# eth_10base-t1s_phy.net
KiCad netlist of a schematic drawn in Altium Designer
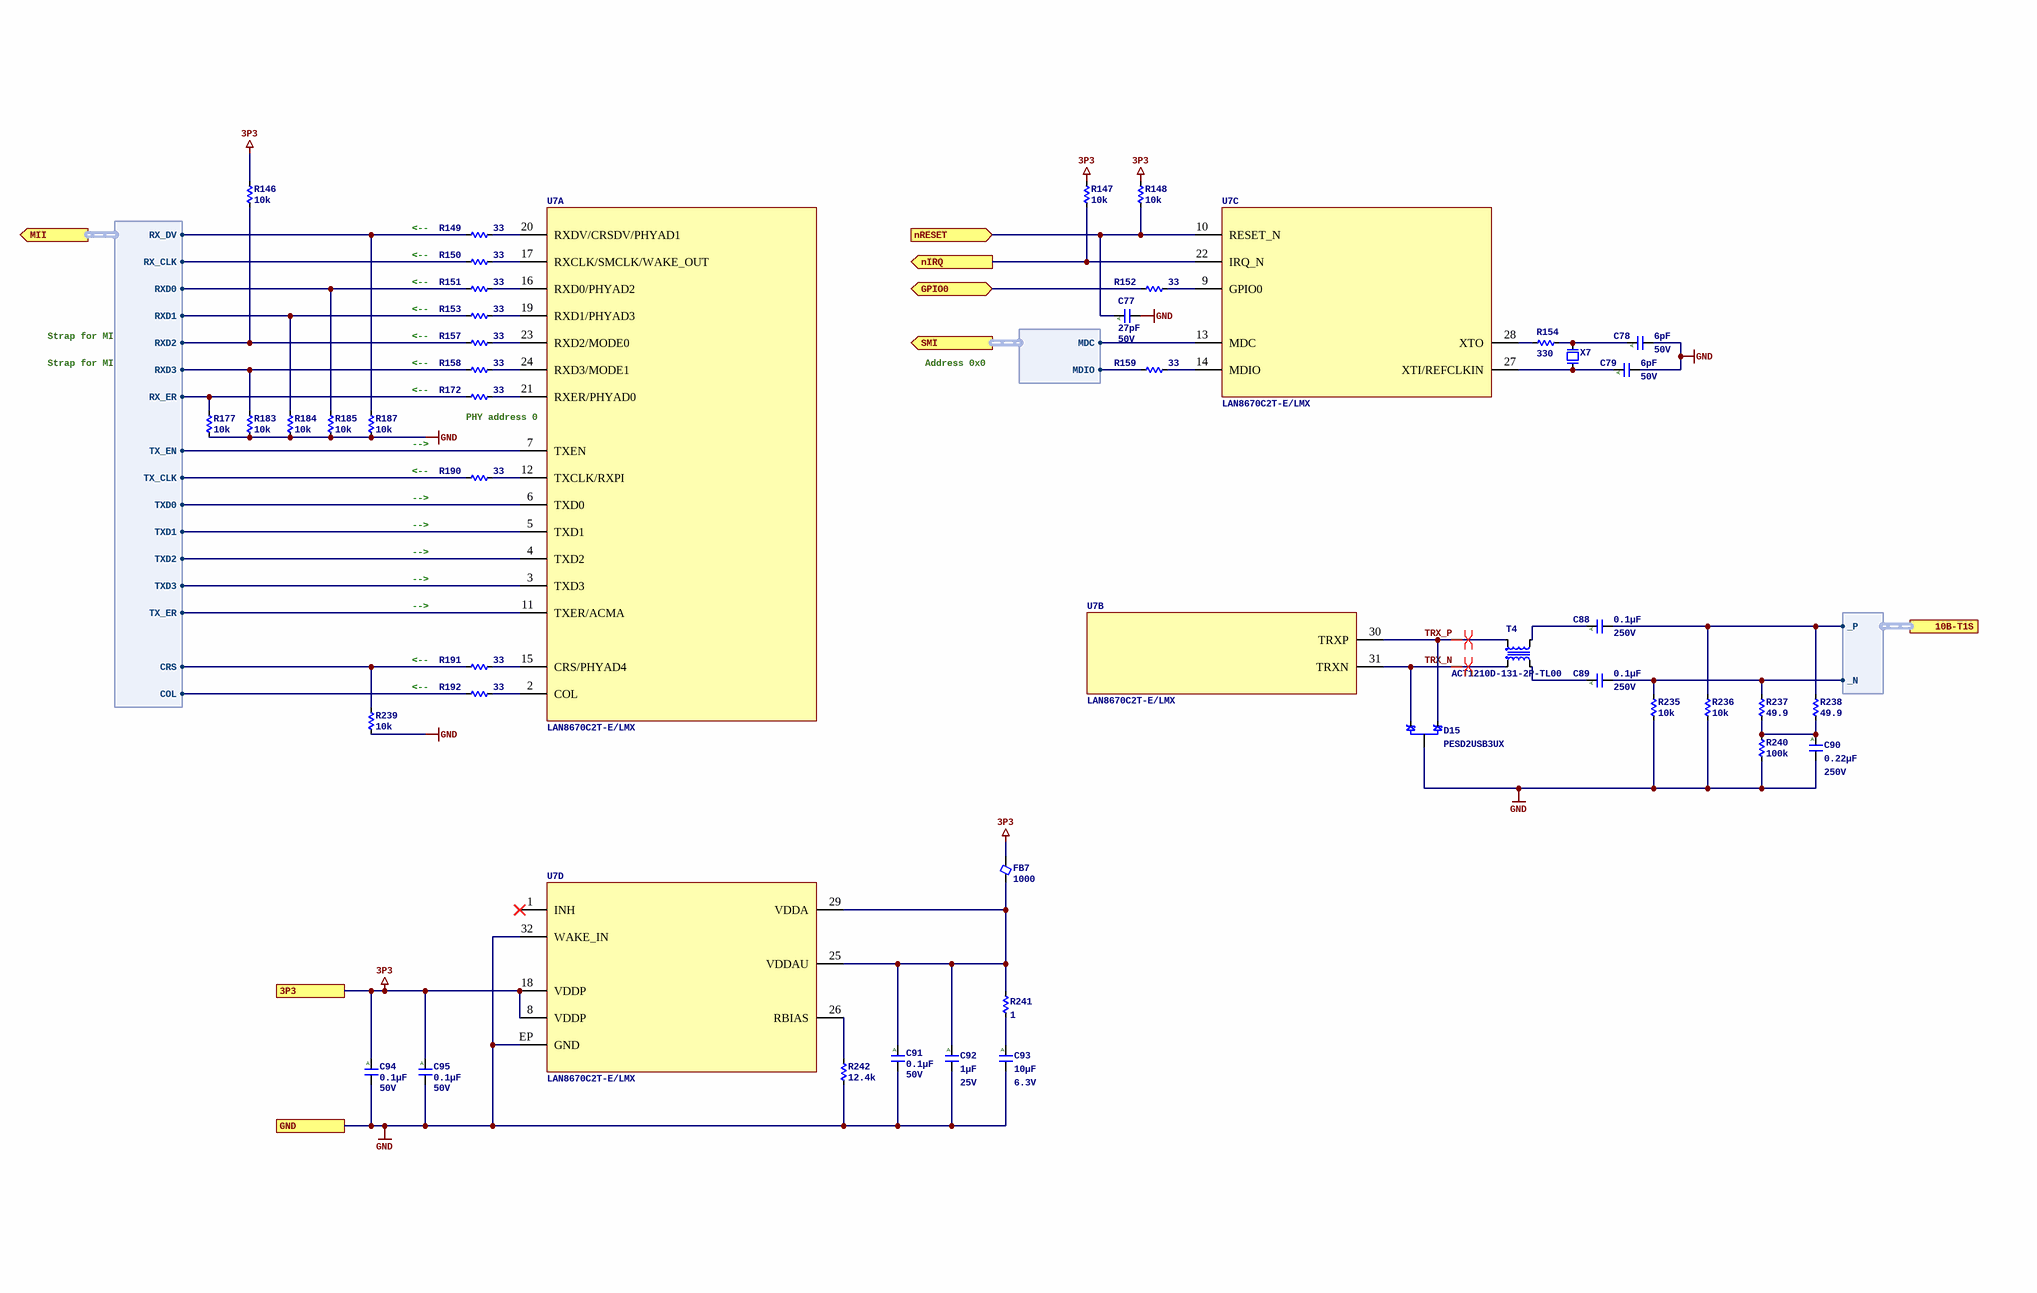
[diagram p0: eth_10base-t1s_phy.SchDoc]

(export (version "E")
  (design (tool "Eeschema 10.0.6"))
  (components
    (comp (ref "C77")
      (value "CGA2B2C0G1H270J050BA")
      (footprint "C0402_0.55MM")
      (description "CAP CER 27PF 50V C0G 0402")
      (fields
        (field (name "CAPACITANCE") "27pF")
        (field (name "VOLTAGE - RATED") "50V")
        (field (name "TOLERANCE") "±5%")
        (field (name "MANUFACTURER") "TDK Corporation")
      )
      (libsource (lib "sscp") (part "__template_cap_auto"))
    )
    (comp (ref "C78")
      (value "CGA2B2C0G1H060D050BA")
      (footprint "C0402_0.55MM")
      (description "CAP CER 6PF 50V C0G 0402")
      (fields
        (field (name "CAPACITANCE") "6pF")
        (field (name "VOLTAGE - RATED") "50V")
        (field (name "TOLERANCE") "±0.5pF")
        (field (name "MANUFACTURER") "TDK Corporation")
      )
      (libsource (lib "sscp") (part "__template_cap_auto"))
    )
    (comp (ref "C79")
      (value "CGA2B2C0G1H060D050BA")
      (footprint "C0402_0.55MM")
      (description "CAP CER 6PF 50V C0G 0402")
      (fields
        (field (name "CAPACITANCE") "6pF")
        (field (name "VOLTAGE - RATED") "50V")
        (field (name "TOLERANCE") "±0.5pF")
        (field (name "MANUFACTURER") "TDK Corporation")
      )
      (libsource (lib "sscp") (part "__template_cap_auto"))
    )
    (comp (ref "C88")
      (value "CGA5L3X7R2E104K160AA")
      (footprint "C1206_1.80MM")
      (description "CAP CER 0.1UF 250V X7R 1206")
      (fields
        (field (name "CAPACITANCE") "0.1µF")
        (field (name "VOLTAGE - RATED") "250V")
        (field (name "TOLERANCE") "±10%")
        (field (name "MANUFACTURER") "TDK Corporation")
      )
      (libsource (lib "sscp") (part "__template_cap_auto"))
    )
    (comp (ref "C89")
      (value "CGA5L3X7R2E104K160AA")
      (footprint "C1206_1.80MM")
      (description "CAP CER 0.1UF 250V X7R 1206")
      (fields
        (field (name "CAPACITANCE") "0.1µF")
        (field (name "VOLTAGE - RATED") "250V")
        (field (name "TOLERANCE") "±10%")
        (field (name "MANUFACTURER") "TDK Corporation")
      )
      (libsource (lib "sscp") (part "__template_cap_auto"))
    )
    (comp (ref "C90")
      (value "CGA6M3X7R2E224K200AA")
      (footprint "C1210_2.20MM")
      (description "CAP CER 0.22UF 250V X7R 1210")
      (fields
        (field (name "CAPACITANCE") "0.22µF")
        (field (name "VOLTAGE - RATED") "250V")
        (field (name "TOLERANCE") "±10%")
        (field (name "MANUFACTURER") "TDK Corporation")
      )
      (libsource (lib "sscp") (part "__template_cap_auto"))
    )
    (comp (ref "C91")
      (value "CGA2B3X7R1H104M050BB")
      (footprint "C0402_0.55MM")
      (description "CAP CER 0.1UF 50V X7R 0402")
      (fields
        (field (name "CAPACITANCE") "0.1µF")
        (field (name "VOLTAGE - RATED") "50V")
        (field (name "TOLERANCE") "±20%")
        (field (name "MANUFACTURER") "TDK Corporation")
      )
      (libsource (lib "sscp") (part "__template_cap_auto"))
    )
    (comp (ref "C92")
      (value "CGJ3E1X7R1E105K080AC")
      (footprint "C0603_0.80MM")
      (description "CAP CER 1UF 25V X7R 0603")
      (fields
        (field (name "CAPACITANCE") "1µF")
        (field (name "VOLTAGE - RATED") "25V")
        (field (name "TOLERANCE") "±10%")
        (field (name "MANUFACTURER") "TDK Corporation")
      )
      (libsource (lib "sscp") (part "__template_cap_auto"))
    )
    (comp (ref "C93")
      (value "CGA4J1X7R0J106M125AC")
      (footprint "C0805_1.45MM")
      (description "CAP CER 10UF 6.3V X7R 0805")
      (fields
        (field (name "CAPACITANCE") "10µF")
        (field (name "VOLTAGE - RATED") "6.3V")
        (field (name "TOLERANCE") "±20%")
        (field (name "MANUFACTURER") "TDK Corporation")
      )
      (libsource (lib "sscp") (part "__template_cap_auto"))
    )
    (comp (ref "C94")
      (value "CGA2B3X7R1H104M050BB")
      (footprint "C0402_0.55MM")
      (description "CAP CER 0.1UF 50V X7R 0402")
      (fields
        (field (name "CAPACITANCE") "0.1µF")
        (field (name "VOLTAGE - RATED") "50V")
        (field (name "TOLERANCE") "±20%")
        (field (name "MANUFACTURER") "TDK Corporation")
      )
      (libsource (lib "sscp") (part "__template_cap_auto"))
    )
    (comp (ref "C95")
      (value "CGA2B3X7R1H104M050BB")
      (footprint "C0402_0.55MM")
      (description "CAP CER 0.1UF 50V X7R 0402")
      (fields
        (field (name "CAPACITANCE") "0.1µF")
        (field (name "VOLTAGE - RATED") "50V")
        (field (name "TOLERANCE") "±20%")
        (field (name "MANUFACTURER") "TDK Corporation")
      )
      (libsource (lib "sscp") (part "__template_cap_auto"))
    )
    (comp (ref "D15")
      (value "PESD2USB3UX")
      (footprint "3SOT23")
      (description "DIODE ESD USB SOT-23")
      (fields (field (name "MANUFACTURER") "Nexperia USA Inc."))
      (libsource (lib "SSCP") (part "TVS_PESD2USB3UX-T"))
    )
    (comp (ref "FB7")
      (value "MPZ2012S102AT000")
      (footprint "FB0805_1.05MM")
      (description "FERRITE BEAD 1 KOHM 0805 1LN")
      (fields
        (field (name "IMPEDANCE (OHMS @ 100MHZ)") "1000")
        (field (name "MANUFACTURER") "TDK Corporation")
      )
      (libsource (lib "sscp") (part "__template_ferrite"))
    )
    (comp (ref "R146")
      (value "ERJ-2RKF1002X")
      (footprint "R0402_0.40MM")
      (description "RES SMD 10K OHM 1% 1/10W 0402")
      (fields
        (field (name "RESISTANCE") "10k")
        (field (name "TOLERANCE") "±1%")
        (field (name "MANUFACTURER") "Panasonic Electronic Components")
      )
      (libsource (lib "sscp") (part "__template_resistor"))
    )
    (comp (ref "R147")
      (value "ERJ-2RKF1002X")
      (footprint "R0402_0.40MM")
      (description "RES SMD 10K OHM 1% 1/10W 0402")
      (fields
        (field (name "RESISTANCE") "10k")
        (field (name "TOLERANCE") "±1%")
        (field (name "MANUFACTURER") "Panasonic Electronic Components")
      )
      (libsource (lib "sscp") (part "__template_resistor"))
    )
    (comp (ref "R148")
      (value "ERJ-2RKF1002X")
      (footprint "R0402_0.40MM")
      (description "RES SMD 10K OHM 1% 1/10W 0402")
      (fields
        (field (name "RESISTANCE") "10k")
        (field (name "TOLERANCE") "±1%")
        (field (name "MANUFACTURER") "Panasonic Electronic Components")
      )
      (libsource (lib "sscp") (part "__template_resistor"))
    )
    (comp (ref "R149")
      (value "ERJ-2RKF33R0X")
      (footprint "R0402_0.40MM")
      (description "RES SMD 33 OHM 1% 1/10W 0402")
      (fields
        (field (name "RESISTANCE") "33")
        (field (name "TOLERANCE") "±1%")
        (field (name "MANUFACTURER") "Panasonic Electronic Components")
      )
      (libsource (lib "sscp") (part "__template_resistor"))
    )
    (comp (ref "R150")
      (value "ERJ-2RKF33R0X")
      (footprint "R0402_0.40MM")
      (description "RES SMD 33 OHM 1% 1/10W 0402")
      (fields
        (field (name "RESISTANCE") "33")
        (field (name "TOLERANCE") "±1%")
        (field (name "MANUFACTURER") "Panasonic Electronic Components")
      )
      (libsource (lib "sscp") (part "__template_resistor"))
    )
    (comp (ref "R151")
      (value "ERJ-2RKF33R0X")
      (footprint "R0402_0.40MM")
      (description "RES SMD 33 OHM 1% 1/10W 0402")
      (fields
        (field (name "RESISTANCE") "33")
        (field (name "TOLERANCE") "±1%")
        (field (name "MANUFACTURER") "Panasonic Electronic Components")
      )
      (libsource (lib "sscp") (part "__template_resistor"))
    )
    (comp (ref "R152")
      (value "ERJ-2RKF33R0X")
      (footprint "R0402_0.40MM")
      (description "RES SMD 33 OHM 1% 1/10W 0402")
      (fields
        (field (name "RESISTANCE") "33")
        (field (name "TOLERANCE") "±1%")
        (field (name "MANUFACTURER") "Panasonic Electronic Components")
      )
      (libsource (lib "sscp") (part "__template_resistor"))
    )
    (comp (ref "R153")
      (value "ERJ-2RKF33R0X")
      (footprint "R0402_0.40MM")
      (description "RES SMD 33 OHM 1% 1/10W 0402")
      (fields
        (field (name "RESISTANCE") "33")
        (field (name "TOLERANCE") "±1%")
        (field (name "MANUFACTURER") "Panasonic Electronic Components")
      )
      (libsource (lib "sscp") (part "__template_resistor"))
    )
    (comp (ref "R154")
      (value "ERJ-PA2F3300X")
      (footprint "R0402_0.40MM")
      (description "RES SMD 330 OHM 1% 1/5W 0402")
      (fields
        (field (name "RESISTANCE") "330")
        (field (name "TOLERANCE") "±1%")
        (field (name "MANUFACTURER") "Panasonic Electronic Components")
      )
      (libsource (lib "sscp") (part "__template_resistor"))
    )
    (comp (ref "R157")
      (value "ERJ-2RKF33R0X")
      (footprint "R0402_0.40MM")
      (description "RES SMD 33 OHM 1% 1/10W 0402")
      (fields
        (field (name "RESISTANCE") "33")
        (field (name "TOLERANCE") "±1%")
        (field (name "MANUFACTURER") "Panasonic Electronic Components")
      )
      (libsource (lib "sscp") (part "__template_resistor"))
    )
    (comp (ref "R158")
      (value "ERJ-2RKF33R0X")
      (footprint "R0402_0.40MM")
      (description "RES SMD 33 OHM 1% 1/10W 0402")
      (fields
        (field (name "RESISTANCE") "33")
        (field (name "TOLERANCE") "±1%")
        (field (name "MANUFACTURER") "Panasonic Electronic Components")
      )
      (libsource (lib "sscp") (part "__template_resistor"))
    )
    (comp (ref "R159")
      (value "ERJ-2RKF33R0X")
      (footprint "R0402_0.40MM")
      (description "RES SMD 33 OHM 1% 1/10W 0402")
      (fields
        (field (name "RESISTANCE") "33")
        (field (name "TOLERANCE") "±1%")
        (field (name "MANUFACTURER") "Panasonic Electronic Components")
      )
      (libsource (lib "sscp") (part "__template_resistor"))
    )
    (comp (ref "R172")
      (value "ERJ-2RKF33R0X")
      (footprint "R0402_0.40MM")
      (description "RES SMD 33 OHM 1% 1/10W 0402")
      (fields
        (field (name "RESISTANCE") "33")
        (field (name "TOLERANCE") "±1%")
        (field (name "MANUFACTURER") "Panasonic Electronic Components")
      )
      (libsource (lib "sscp") (part "__template_resistor"))
    )
    (comp (ref "R177")
      (value "ERJ-2RKF1002X")
      (footprint "R0402_0.40MM")
      (description "RES SMD 10K OHM 1% 1/10W 0402")
      (fields
        (field (name "RESISTANCE") "10k")
        (field (name "TOLERANCE") "±1%")
        (field (name "MANUFACTURER") "Panasonic Electronic Components")
      )
      (libsource (lib "sscp") (part "__template_resistor"))
    )
    (comp (ref "R183")
      (value "ERJ-2RKF1002X")
      (footprint "R0402_0.40MM")
      (description "RES SMD 10K OHM 1% 1/10W 0402")
      (fields
        (field (name "RESISTANCE") "10k")
        (field (name "TOLERANCE") "±1%")
        (field (name "MANUFACTURER") "Panasonic Electronic Components")
      )
      (libsource (lib "sscp") (part "__template_resistor"))
    )
    (comp (ref "R184")
      (value "ERJ-2RKF1002X")
      (footprint "R0402_0.40MM")
      (description "RES SMD 10K OHM 1% 1/10W 0402")
      (fields
        (field (name "RESISTANCE") "10k")
        (field (name "TOLERANCE") "±1%")
        (field (name "MANUFACTURER") "Panasonic Electronic Components")
      )
      (libsource (lib "sscp") (part "__template_resistor"))
    )
    (comp (ref "R185")
      (value "ERJ-2RKF1002X")
      (footprint "R0402_0.40MM")
      (description "RES SMD 10K OHM 1% 1/10W 0402")
      (fields
        (field (name "RESISTANCE") "10k")
        (field (name "TOLERANCE") "±1%")
        (field (name "MANUFACTURER") "Panasonic Electronic Components")
      )
      (libsource (lib "sscp") (part "__template_resistor"))
    )
    (comp (ref "R187")
      (value "ERJ-2RKF1002X")
      (footprint "R0402_0.40MM")
      (description "RES SMD 10K OHM 1% 1/10W 0402")
      (fields
        (field (name "RESISTANCE") "10k")
        (field (name "TOLERANCE") "±1%")
        (field (name "MANUFACTURER") "Panasonic Electronic Components")
      )
      (libsource (lib "sscp") (part "__template_resistor"))
    )
    (comp (ref "R190")
      (value "ERJ-2RKF33R0X")
      (footprint "R0402_0.40MM")
      (description "RES SMD 33 OHM 1% 1/10W 0402")
      (fields
        (field (name "RESISTANCE") "33")
        (field (name "TOLERANCE") "±1%")
        (field (name "MANUFACTURER") "Panasonic Electronic Components")
      )
      (libsource (lib "sscp") (part "__template_resistor"))
    )
    (comp (ref "R191")
      (value "ERJ-2RKF33R0X")
      (footprint "R0402_0.40MM")
      (description "RES SMD 33 OHM 1% 1/10W 0402")
      (fields
        (field (name "RESISTANCE") "33")
        (field (name "TOLERANCE") "±1%")
        (field (name "MANUFACTURER") "Panasonic Electronic Components")
      )
      (libsource (lib "sscp") (part "__template_resistor"))
    )
    (comp (ref "R192")
      (value "ERJ-2RKF33R0X")
      (footprint "R0402_0.40MM")
      (description "RES SMD 33 OHM 1% 1/10W 0402")
      (fields
        (field (name "RESISTANCE") "33")
        (field (name "TOLERANCE") "±1%")
        (field (name "MANUFACTURER") "Panasonic Electronic Components")
      )
      (libsource (lib "sscp") (part "__template_resistor"))
    )
    (comp (ref "R235")
      (value "ERJ-8ENF1002V")
      (footprint "R1206_0.70MM")
      (description "RES SMD 10K OHM 1% 1/4W 1206")
      (fields
        (field (name "RESISTANCE") "10k")
        (field (name "TOLERANCE") "±1%")
        (field (name "MANUFACTURER") "Panasonic Electronic Components")
      )
      (libsource (lib "sscp") (part "__template_resistor"))
    )
    (comp (ref "R236")
      (value "ERJ-8ENF1002V")
      (footprint "R1206_0.70MM")
      (description "RES SMD 10K OHM 1% 1/4W 1206")
      (fields
        (field (name "RESISTANCE") "10k")
        (field (name "TOLERANCE") "±1%")
        (field (name "MANUFACTURER") "Panasonic Electronic Components")
      )
      (libsource (lib "sscp") (part "__template_resistor"))
    )
    (comp (ref "R237")
      (value "ERJ-8ENF49R9V")
      (footprint "R1206_0.70MM")
      (description "RES SMD 49.9 OHM 1% 1/4W 1206")
      (fields
        (field (name "RESISTANCE") "49.9")
        (field (name "TOLERANCE") "±1%")
        (field (name "MANUFACTURER") "Panasonic Electronic Components")
      )
      (libsource (lib "sscp") (part "__template_resistor"))
    )
    (comp (ref "R238")
      (value "ERJ-8ENF49R9V")
      (footprint "R1206_0.70MM")
      (description "RES SMD 49.9 OHM 1% 1/4W 1206")
      (fields
        (field (name "RESISTANCE") "49.9")
        (field (name "TOLERANCE") "±1%")
        (field (name "MANUFACTURER") "Panasonic Electronic Components")
      )
      (libsource (lib "sscp") (part "__template_resistor"))
    )
    (comp (ref "R239")
      (value "ERJ-2RKF1002X")
      (footprint "R0402_0.40MM")
      (description "RES SMD 10K OHM 1% 1/10W 0402")
      (fields
        (field (name "RESISTANCE") "10k")
        (field (name "TOLERANCE") "±1%")
        (field (name "MANUFACTURER") "Panasonic Electronic Components")
      )
      (libsource (lib "sscp") (part "__template_resistor"))
    )
    (comp (ref "R240")
      (value "ERJ-8ENF1003V")
      (footprint "R1206_0.70MM")
      (description "RES SMD 100K OHM 1% 1/4W 1206")
      (fields
        (field (name "RESISTANCE") "100k")
        (field (name "TOLERANCE") "±1%")
        (field (name "MANUFACTURER") "Panasonic Electronic Components")
      )
      (libsource (lib "sscp") (part "__template_resistor"))
    )
    (comp (ref "R241")
      (value "ERJ-2BQF1R0X")
      (footprint "R0402_0.40MM")
      (description "RES SMD 1 OHM 1% 1/6W 0402")
      (fields
        (field (name "RESISTANCE") "1")
        (field (name "TOLERANCE") "±1%")
        (field (name "MANUFACTURER") "Panasonic Electronic Components")
      )
      (libsource (lib "sscp") (part "__template_resistor"))
    )
    (comp (ref "R242")
      (value "ERJ-2RKF1242X")
      (footprint "R0402_0.40MM")
      (description "RES SMD 12.4K OHM 1% 1/10W 0402")
      (fields
        (field (name "RESISTANCE") "12.4k")
        (field (name "TOLERANCE") "±1%")
        (field (name "MANUFACTURER") "Panasonic Electronic Components")
      )
      (libsource (lib "sscp") (part "__template_resistor"))
    )
    (comp (ref "T4")
      (value "ACT1210D-131-2P-TL00")
      (footprint "CHOKE_ACT1210D-131-2P-TL00")
      (description "130 µH @ 100 kHz 2 Line Common Mode Choke Surface Mount 6.7 kOhms @ 10 MHz 115mA DCR 3.5Ohm")
      (fields (field (name "MANUFACTURER") "TDK Corporation"))
      (libsource (lib "SSCP") (part "CHOKE_ACT1210D-131-2P-TL00"))
    )
    (comp (ref "U7")
      (value "LAN8670C2T-E/LMX")
      (footprint "QFN50P500X500X90-32N")
      (description "10BASE-T1S PHY WITH MII/RMII \"1/1 Transceiver Full, Half Ethernet 32-VQFN (5x5)\"")
      (fields (field (name "MANUFACTURER") "Microchip"))
      (libsource (lib "") (part "ETH_PHY_LAN8670C2T-E/LMX_1"))
    )
    (comp (ref "X7")
      (value "XTAL_XRCGB25M000F3A00R0")
      (footprint "4_SMD_2.0X1.6MM")
      (description "CRYSTAL 25.000MHZ 6PF SMD")
      (fields
        (field (name "MANUFACTURER") "Murata")
        (field (name "MANUFACTURER PART NUMBER") "XRCGB25M000F3A00R0")
      )
      (libsource (lib "SSCP") (part "XTAL_XRCGB25M000F3A00R0"))
    )
  )
  (nets
    (net (code "4") (name "/COL") (class "Default") (node (ref "R192") (pin "2") (pintype "passive")))
    (net (code "5") (name "/CRS") (class "Default")
      (node (ref "R191") (pin "2") (pintype "passive"))
      (node (ref "R239") (pin "1") (pintype "passive"))
    )
    (net (code "6") (name "/GPIO0") (class "Default") (node (ref "R152") (pin "2") (pintype "passive")))
    (net (code "7") (name "/MDC") (class "Default")
      (node (ref "U7") (pin "13") (pinfunction "MDC_13") (pintype "passive"))
    )
    (net (code "8") (name "/MDIO") (class "Default") (node (ref "R159") (pin "2") (pintype "passive")))
    (net (code "9") (name "/RXD0") (class "Default")
      (node (ref "R151") (pin "2") (pintype "passive"))
      (node (ref "R185") (pin "1") (pintype "passive"))
    )
    (net (code "10") (name "/RXD1") (class "Default")
      (node (ref "R153") (pin "2") (pintype "passive"))
      (node (ref "R184") (pin "1") (pintype "passive"))
    )
    (net (code "11") (name "/RXD2") (class "Default")
      (node (ref "R146") (pin "2") (pintype "passive"))
      (node (ref "R157") (pin "2") (pintype "passive"))
    )
    (net (code "12") (name "/RXD3") (class "Default")
      (node (ref "R158") (pin "2") (pintype "passive"))
      (node (ref "R183") (pin "1") (pintype "passive"))
    )
    (net (code "13") (name "/RX_CLK") (class "Default") (node (ref "R150") (pin "2") (pintype "passive")))
    (net (code "14") (name "/RX_DV") (class "Default")
      (node (ref "R149") (pin "2") (pintype "passive"))
      (node (ref "R187") (pin "1") (pintype "passive"))
    )
    (net (code "15") (name "/RX_ER") (class "Default")
      (node (ref "R172") (pin "2") (pintype "passive"))
      (node (ref "R177") (pin "1") (pintype "passive"))
    )
    (net (code "16") (name "/TRX_N") (class "Default")
      (node (ref "D15") (pin "1") (pintype "passive"))
      (node (ref "T4") (pin "2") (pintype "passive"))
      (node (ref "U7") (pin "31") (pinfunction "TRXN_31") (pintype "passive"))
    )
    (net (code "17") (name "/TRX_P") (class "Default")
      (node (ref "D15") (pin "2") (pintype "passive"))
      (node (ref "T4") (pin "1") (pintype "passive"))
      (node (ref "U7") (pin "30") (pinfunction "TRXP_30") (pintype "passive"))
    )
    (net (code "18") (name "/TXD0") (class "Default")
      (node (ref "U7") (pin "6") (pinfunction "TXD0_6") (pintype "passive"))
    )
    (net (code "19") (name "/TXD1") (class "Default")
      (node (ref "U7") (pin "5") (pinfunction "TXD1_5") (pintype "passive"))
    )
    (net (code "20") (name "/TXD2") (class "Default")
      (node (ref "U7") (pin "4") (pinfunction "TXD2_4") (pintype "passive"))
    )
    (net (code "21") (name "/TXD3") (class "Default")
      (node (ref "U7") (pin "3") (pinfunction "TXD3_3") (pintype "passive"))
    )
    (net (code "22") (name "/TX_CLK") (class "Default") (node (ref "R190") (pin "2") (pintype "passive")))
    (net (code "23") (name "/TX_EN") (class "Default")
      (node (ref "U7") (pin "7") (pinfunction "TXEN_7") (pintype "passive"))
    )
    (net (code "24") (name "/TX_ER") (class "Default")
      (node (ref "U7") (pin "11") (pinfunction "TXER/ACMA_11") (pintype "passive"))
    )
    (net (code "25") (name "/_N") (class "Default")
      (node (ref "C89") (pin "2") (pintype "passive"))
      (node (ref "R235") (pin "1") (pintype "passive"))
      (node (ref "R237") (pin "1") (pintype "passive"))
    )
    (net (code "26") (name "/_P") (class "Default")
      (node (ref "C88") (pin "2") (pintype "passive"))
      (node (ref "R236") (pin "1") (pintype "passive"))
      (node (ref "R238") (pin "1") (pintype "passive"))
    )
    (net (code "27") (name "/nIRQ") (class "Default")
      (node (ref "R147") (pin "2") (pintype "passive"))
      (node (ref "U7") (pin "22") (pinfunction "IRQ_N_22") (pintype "passive"))
    )
    (net (code "28") (name "/nRESET") (class "Default")
      (node (ref "C77") (pin "1") (pintype "passive"))
      (node (ref "R148") (pin "2") (pintype "passive"))
      (node (ref "U7") (pin "10") (pinfunction "RESET_N_10") (pintype "passive"))
    )
    (net (code "32") (name "3P3") (class "Default")
      (node (ref "C94") (pin "1") (pintype "passive"))
      (node (ref "C95") (pin "1") (pintype "passive"))
      (node (ref "FB7") (pin "2") (pintype "passive"))
      (node (ref "R146") (pin "1") (pintype "passive"))
      (node (ref "R147") (pin "1") (pintype "passive"))
      (node (ref "R148") (pin "1") (pintype "passive"))
      (node (ref "U7") (pin "18") (pinfunction "VDDP_18") (pintype "passive"))
      (node (ref "U7") (pin "8") (pinfunction "VDDP_8") (pintype "passive"))
    )
    (net (code "33") (name "GND") (class "Default")
      (node (ref "C77") (pin "2") (pintype "passive"))
      (node (ref "C78") (pin "2") (pintype "passive"))
      (node (ref "C79") (pin "2") (pintype "passive"))
      (node (ref "C90") (pin "2") (pintype "passive"))
      (node (ref "C91") (pin "2") (pintype "passive"))
      (node (ref "C92") (pin "2") (pintype "passive"))
      (node (ref "C93") (pin "2") (pintype "passive"))
      (node (ref "C94") (pin "2") (pintype "passive"))
      (node (ref "C95") (pin "2") (pintype "passive"))
      (node (ref "D15") (pin "3") (pintype "passive"))
      (node (ref "R177") (pin "2") (pintype "passive"))
      (node (ref "R183") (pin "2") (pintype "passive"))
      (node (ref "R184") (pin "2") (pintype "passive"))
      (node (ref "R185") (pin "2") (pintype "passive"))
      (node (ref "R187") (pin "2") (pintype "passive"))
      (node (ref "R235") (pin "2") (pintype "passive"))
      (node (ref "R236") (pin "2") (pintype "passive"))
      (node (ref "R239") (pin "2") (pintype "passive"))
      (node (ref "R240") (pin "2") (pintype "passive"))
      (node (ref "R242") (pin "2") (pintype "passive"))
      (node (ref "U7") (pin "32") (pinfunction "WAKE_IN_32") (pintype "passive"))
      (node (ref "U7") (pin "EP") (pinfunction "GND_EP") (pintype "passive"))
    )
    (net (code "34") (name "Net-(C78-Pad1)") (class "Default")
      (node (ref "C78") (pin "1") (pintype "passive"))
      (node (ref "R154") (pin "2") (pintype "passive"))
      (node (ref "X7") (pin "3") (pinfunction "3_3") (pintype "passive"))
    )
    (net (code "35") (name "Net-(C88-Pad1)") (class "Default")
      (node (ref "C88") (pin "1") (pintype "passive"))
      (node (ref "T4") (pin "4") (pintype "passive"))
    )
    (net (code "36") (name "Net-(C89-Pad1)") (class "Default")
      (node (ref "C89") (pin "1") (pintype "passive"))
      (node (ref "T4") (pin "3") (pintype "passive"))
    )
    (net (code "37") (name "Net-(C90-Pad1)") (class "Default")
      (node (ref "C90") (pin "1") (pintype "passive"))
      (node (ref "R237") (pin "2") (pintype "passive"))
      (node (ref "R238") (pin "2") (pintype "passive"))
      (node (ref "R240") (pin "1") (pintype "passive"))
    )
    (net (code "38") (name "Net-(C93-Pad1)") (class "Default")
      (node (ref "C93") (pin "1") (pintype "passive"))
      (node (ref "R241") (pin "1") (pintype "passive"))
    )
    (net (code "39") (name "Net-(U7A-COL)") (class "Default")
      (node (ref "R192") (pin "1") (pintype "passive"))
      (node (ref "U7") (pin "2") (pinfunction "COL_2") (pintype "passive"))
    )
    (net (code "40") (name "Net-(U7A-CRS{slash}PHYAD4)") (class "Default")
      (node (ref "R191") (pin "1") (pintype "passive"))
      (node (ref "U7") (pin "15") (pinfunction "CRS/PHYAD4_15") (pintype "passive"))
    )
    (net (code "41") (name "Net-(U7A-RXCLK{slash}SMCLK{slash}WAKE_OUT)") (class "Default")
      (node (ref "R150") (pin "1") (pintype "passive"))
      (node (ref "U7") (pin "17") (pinfunction "RXCLK/SMCLK/WAKE_OUT_17") (pintype "passive"))
    )
    (net (code "42") (name "Net-(U7A-RXD0{slash}PHYAD2)") (class "Default")
      (node (ref "R151") (pin "1") (pintype "passive"))
      (node (ref "U7") (pin "16") (pinfunction "RXD0/PHYAD2_16") (pintype "passive"))
    )
    (net (code "43") (name "Net-(U7A-RXD1{slash}PHYAD3)") (class "Default")
      (node (ref "R153") (pin "1") (pintype "passive"))
      (node (ref "U7") (pin "19") (pinfunction "RXD1/PHYAD3_19") (pintype "passive"))
    )
    (net (code "44") (name "Net-(U7A-RXD2{slash}MODE0)") (class "Default")
      (node (ref "R157") (pin "1") (pintype "passive"))
      (node (ref "U7") (pin "23") (pinfunction "RXD2/MODE0_23") (pintype "passive"))
    )
    (net (code "45") (name "Net-(U7A-RXD3{slash}MODE1)") (class "Default")
      (node (ref "R158") (pin "1") (pintype "passive"))
      (node (ref "U7") (pin "24") (pinfunction "RXD3/MODE1_24") (pintype "passive"))
    )
    (net (code "46") (name "Net-(U7A-RXDV{slash}CRSDV{slash}PHYAD1)") (class "Default")
      (node (ref "R149") (pin "1") (pintype "passive"))
      (node (ref "U7") (pin "20") (pinfunction "RXDV/CRSDV/PHYAD1_20") (pintype "passive"))
    )
    (net (code "47") (name "Net-(U7A-RXER{slash}PHYAD0)") (class "Default")
      (node (ref "R172") (pin "1") (pintype "passive"))
      (node (ref "U7") (pin "21") (pinfunction "RXER/PHYAD0_21") (pintype "passive"))
    )
    (net (code "48") (name "Net-(U7A-TXCLK{slash}RXPI)") (class "Default")
      (node (ref "R190") (pin "1") (pintype "passive"))
      (node (ref "U7") (pin "12") (pinfunction "TXCLK/RXPI_12") (pintype "passive"))
    )
    (net (code "49") (name "Net-(U7C-GPIO0)") (class "Default")
      (node (ref "R152") (pin "1") (pintype "passive"))
      (node (ref "U7") (pin "9") (pinfunction "GPIO0_9") (pintype "passive"))
    )
    (net (code "50") (name "Net-(U7C-MDIO)") (class "Default")
      (node (ref "R159") (pin "1") (pintype "passive"))
      (node (ref "U7") (pin "14") (pinfunction "MDIO_14") (pintype "passive"))
    )
    (net (code "51") (name "Net-(U7C-XTI{slash}REFCLKIN)") (class "Default")
      (node (ref "C79") (pin "1") (pintype "passive"))
      (node (ref "U7") (pin "27") (pinfunction "XTI/REFCLKIN_27") (pintype "passive"))
      (node (ref "X7") (pin "1") (pinfunction "1_1") (pintype "passive"))
    )
    (net (code "52") (name "Net-(U7C-XTO)") (class "Default")
      (node (ref "R154") (pin "1") (pintype "passive"))
      (node (ref "U7") (pin "28") (pinfunction "XTO_28") (pintype "passive"))
    )
    (net (code "53") (name "Net-(U7D-RBIAS)") (class "Default")
      (node (ref "R242") (pin "1") (pintype "passive"))
      (node (ref "U7") (pin "26") (pinfunction "RBIAS_26") (pintype "passive"))
    )
    (net (code "54") (name "Net-(U7D-VDDA)") (class "Default")
      (node (ref "C91") (pin "1") (pintype "passive"))
      (node (ref "C92") (pin "1") (pintype "passive"))
      (node (ref "FB7") (pin "1") (pintype "passive"))
      (node (ref "R241") (pin "2") (pintype "passive"))
      (node (ref "U7") (pin "25") (pinfunction "VDDAU_25") (pintype "passive"))
      (node (ref "U7") (pin "29") (pinfunction "VDDA_29") (pintype "passive"))
    )
    (net (code "55") (name "unconnected-(U7D-INH-Pad1)") (class "Default")
      (node (ref "U7") (pin "1") (pinfunction "INH_1") (pintype "passive+no_connect"))
    )
  )
)
